# v1_0.net
KiCad netlist of a schematic drawn in Altium Designer
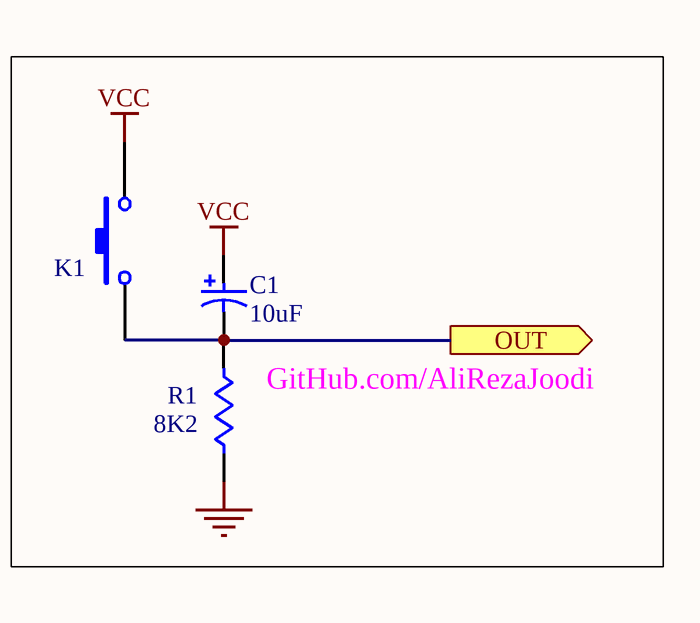
[diagram p0: v1.0.SchDoc]

(export (version "E")
  (design (tool "Eeschema 10.0.6"))
  (components
    (comp (ref "C1")
      (value "10uF")
      (footprint "C_THD_EL_(P2.54-D6-H11)")
      (description "Capacitor, Electrolytic")
      (libsource (lib "Passive") (part "Capacitor_Electrolytic"))
    )
    (comp (ref "K1")
      (value "SW-PB")
      (footprint "SPST-2_2")
      (description "Switch")
      (fields (field (name "MANUFACTURER") "Generic Components") (field (name "PUBLISHER") "Altium Limited"))
      (libsource (lib "Miscellaneous Devices") (part "SW-PB"))
    )
    (comp (ref "R1")
      (value "8K2")
      (footprint "AXIAL-0.4")
      (description "Resistor")
      (fields (field (name "MANUFACTURER") "Generic Components") (field (name "PUBLISHER") "Altium Limited"))
      (libsource (lib "Miscellaneous Devices") (part "Res1"))
    )
  )
  (nets
    (net (code "1") (name "/OUT") (class "Default")
      (node (ref "C1") (pin "2") (pinfunction "2_2") (pintype "passive"))
      (node (ref "K1") (pin "1") (pinfunction "1_1") (pintype "passive"))
      (node (ref "R1") (pin "2") (pinfunction "2_2") (pintype "passive"))
    )
    (net (code "2") (name "GND") (class "Default")
      (node (ref "R1") (pin "1") (pinfunction "1_1") (pintype "passive"))
    )
    (net (code "3") (name "VCC") (class "Default")
      (node (ref "C1") (pin "1") (pinfunction "1_1") (pintype "passive"))
      (node (ref "K1") (pin "2") (pinfunction "2_2") (pintype "passive"))
    )
  )
)
